# stm32f401_test_module.net
KiCad netlist of a schematic drawn in EAGLE
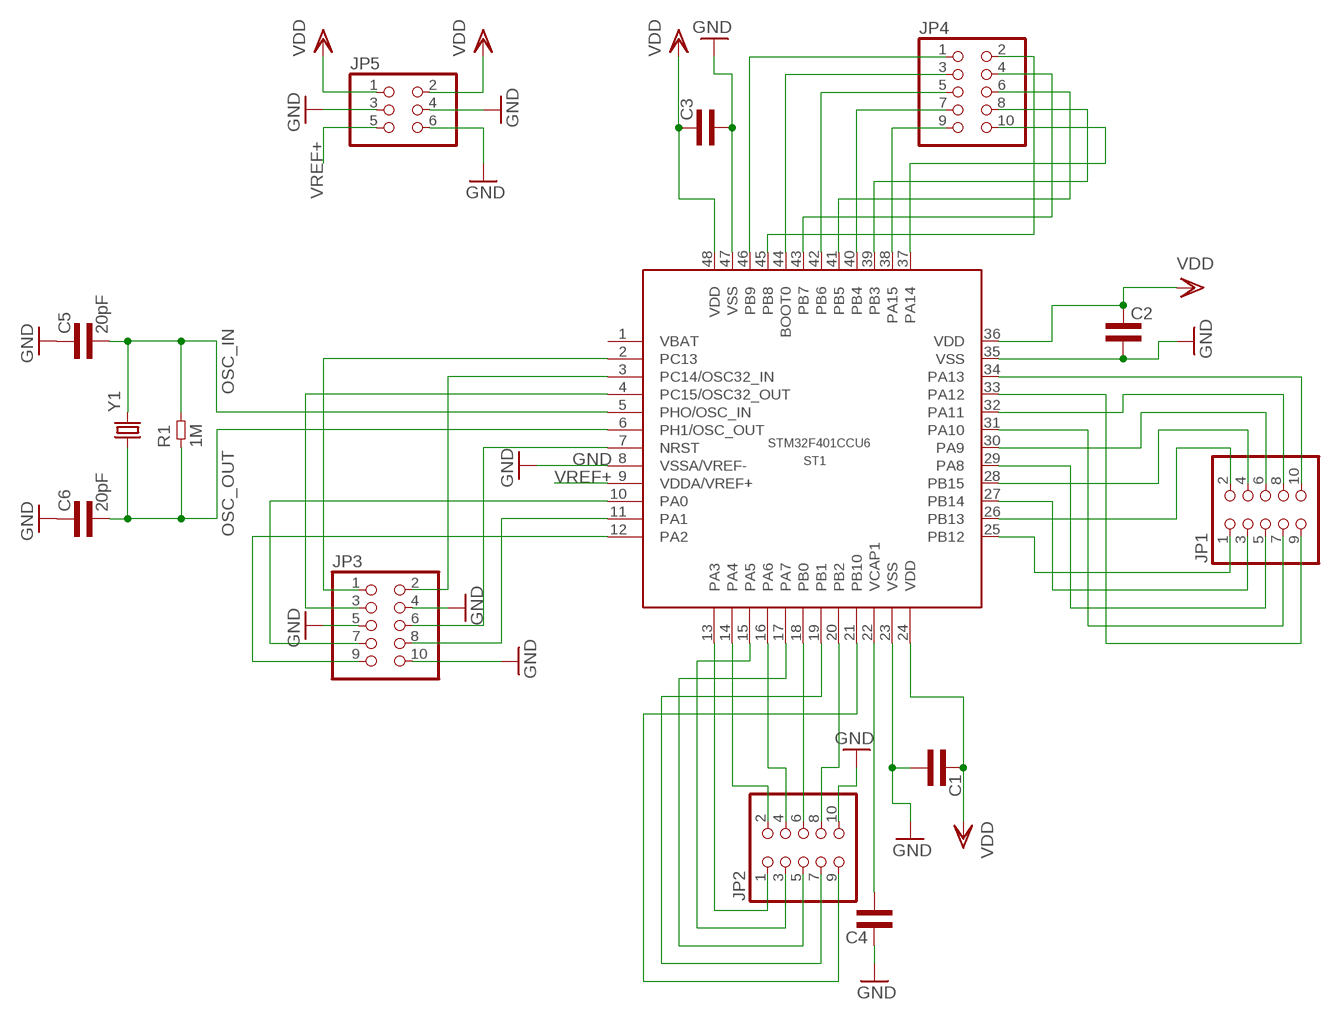
[diagram p0: schematic, sheet 1]

(export (version "E")
  (design (tool "Eeschema 10.0.6"))
  (components
    (comp (ref "C1")
      (value "CAP0402L3")
      (footprint "eagle-import:0402L3")
      (libsource (lib "eagle-import") (part "CAP0402L3"))
    )
    (comp (ref "C2")
      (value "CAP0402L3")
      (footprint "eagle-import:0402L3")
      (libsource (lib "eagle-import") (part "CAP0402L3"))
    )
    (comp (ref "C3")
      (value "CAP0402L3")
      (footprint "eagle-import:0402L3")
      (libsource (lib "eagle-import") (part "CAP0402L3"))
    )
    (comp (ref "C4")
      (value "CAP0402L3")
      (footprint "eagle-import:0402L3")
      (libsource (lib "eagle-import") (part "CAP0402L3"))
    )
    (comp (ref "C5")
      (value "20pF")
      (footprint "eagle-import:0603L3")
      (libsource (lib "eagle-import") (part "CAP0603L3"))
    )
    (comp (ref "C6")
      (value "20pF")
      (footprint "eagle-import:0603L3")
      (libsource (lib "eagle-import") (part "CAP0603L3"))
    )
    (comp (ref "JP1")
      (value "PINHD-2X5")
      (footprint "eagle-import:2X05")
      (libsource (lib "eagle-import") (part "PINHD-2X5"))
    )
    (comp (ref "JP2")
      (value "PINHD-2X5")
      (footprint "eagle-import:2X05")
      (libsource (lib "eagle-import") (part "PINHD-2X5"))
    )
    (comp (ref "JP3")
      (value "PINHD-2X5")
      (footprint "eagle-import:2X05")
      (libsource (lib "eagle-import") (part "PINHD-2X5"))
    )
    (comp (ref "JP4")
      (value "PINHD-2X5")
      (footprint "eagle-import:2X05")
      (libsource (lib "eagle-import") (part "PINHD-2X5"))
    )
    (comp (ref "JP5")
      (value "PINHD-2X3")
      (footprint "eagle-import:2X03")
      (libsource (lib "eagle-import") (part "PINHD-2X3"))
    )
    (comp (ref "R1")
      (value "1M")
      (footprint "eagle-import:0603L3")
      (libsource (lib "eagle-import") (part "RES0603L3"))
    )
    (comp (ref "ST1")
      (value "STM32F401CCU6")
      (footprint "eagle-import:UFQFPN48")
      (libsource (lib "eagle-import") (part "STM32F401CCU6"))
    )
    (comp (ref "Y1")
      (value "CRYSTALHC49US")
      (footprint "eagle-import:HC49US")
      (libsource (lib "eagle-import") (part "CRYSTALHC49US"))
    )
  )
  (nets
    (net (code "1") (name "/OSC_IN") (class "Default")
      (node (ref "C5") (pin "P$2") (pinfunction "2_P$2") (pintype "bidirectional"))
      (node (ref "R1") (pin "P$2") (pinfunction "2_P$2") (pintype "bidirectional"))
      (node (ref "ST1") (pin "5") (pinfunction "PHO/OSC_IN_5") (pintype "bidirectional"))
      (node (ref "Y1") (pin "2") (pinfunction "2_2") (pintype "passive"))
    )
    (net (code "2") (name "/OSC_OUT") (class "Default")
      (node (ref "C6") (pin "P$2") (pinfunction "2_P$2") (pintype "bidirectional"))
      (node (ref "R1") (pin "P$1") (pinfunction "1_P$1") (pintype "bidirectional"))
      (node (ref "ST1") (pin "6") (pinfunction "PH1/OSC_OUT_6") (pintype "bidirectional"))
      (node (ref "Y1") (pin "1") (pinfunction "1_1") (pintype "passive"))
    )
    (net (code "3") (name "/VREF+") (class "Default")
      (node (ref "JP5") (pin "5") (pinfunction "5_5") (pintype "passive"))
      (node (ref "ST1") (pin "9") (pinfunction "VDDA/VREF+_9") (pintype "bidirectional"))
    )
    (net (code "4") (name "GND") (class "Default")
      (node (ref "C1") (pin "P$2") (pinfunction "2_P$2") (pintype "bidirectional"))
      (node (ref "C2") (pin "P$2") (pinfunction "2_P$2") (pintype "bidirectional"))
      (node (ref "C3") (pin "P$2") (pinfunction "2_P$2") (pintype "bidirectional"))
      (node (ref "C4") (pin "P$1") (pinfunction "1_P$1") (pintype "bidirectional"))
      (node (ref "C5") (pin "P$1") (pinfunction "1_P$1") (pintype "bidirectional"))
      (node (ref "C6") (pin "P$1") (pinfunction "1_P$1") (pintype "bidirectional"))
      (node (ref "JP2") (pin "10") (pinfunction "10_10") (pintype "passive"))
      (node (ref "JP3") (pin "10") (pinfunction "10_10") (pintype "passive"))
      (node (ref "JP3") (pin "4") (pinfunction "4_4") (pintype "passive"))
      (node (ref "JP3") (pin "5") (pinfunction "5_5") (pintype "passive"))
      (node (ref "JP5") (pin "3") (pinfunction "3_3") (pintype "passive"))
      (node (ref "JP5") (pin "4") (pinfunction "4_4") (pintype "passive"))
      (node (ref "JP5") (pin "6") (pinfunction "6_6") (pintype "passive"))
      (node (ref "ST1") (pin "23") (pinfunction "VSS_23") (pintype "bidirectional"))
      (node (ref "ST1") (pin "35") (pinfunction "VSS_35") (pintype "bidirectional"))
      (node (ref "ST1") (pin "47") (pinfunction "VSS_47") (pintype "bidirectional"))
      (node (ref "ST1") (pin "8") (pinfunction "VSSA/VREF-_8") (pintype "bidirectional"))
    )
    (net (code "5") (name "Net-(C4-2)") (class "Default")
      (node (ref "C4") (pin "P$2") (pinfunction "2_P$2") (pintype "bidirectional"))
      (node (ref "ST1") (pin "22") (pinfunction "VCAP1_22") (pintype "bidirectional"))
    )
    (net (code "6") (name "Net-(ST1-BOOT0)") (class "Default")
      (node (ref "JP4") (pin "3") (pinfunction "3_3") (pintype "passive"))
      (node (ref "ST1") (pin "44") (pinfunction "BOOT0_44") (pintype "bidirectional"))
    )
    (net (code "7") (name "Net-(ST1-NRST)") (class "Default")
      (node (ref "JP3") (pin "6") (pinfunction "6_6") (pintype "passive"))
      (node (ref "ST1") (pin "7") (pinfunction "NRST_7") (pintype "bidirectional"))
    )
    (net (code "8") (name "Net-(ST1-PA0)") (class "Default")
      (node (ref "JP3") (pin "7") (pinfunction "7_7") (pintype "passive"))
      (node (ref "ST1") (pin "10") (pinfunction "PA0_10") (pintype "bidirectional"))
    )
    (net (code "9") (name "Net-(ST1-PA1)") (class "Default")
      (node (ref "JP3") (pin "8") (pinfunction "8_8") (pintype "passive"))
      (node (ref "ST1") (pin "11") (pinfunction "PA1_11") (pintype "bidirectional"))
    )
    (net (code "10") (name "Net-(ST1-PA2)") (class "Default")
      (node (ref "JP3") (pin "9") (pinfunction "9_9") (pintype "passive"))
      (node (ref "ST1") (pin "12") (pinfunction "PA2_12") (pintype "bidirectional"))
    )
    (net (code "11") (name "Net-(ST1-PA3)") (class "Default")
      (node (ref "JP2") (pin "1") (pinfunction "1_1") (pintype "passive"))
      (node (ref "ST1") (pin "13") (pinfunction "PA3_13") (pintype "bidirectional"))
    )
    (net (code "12") (name "Net-(ST1-PA4)") (class "Default")
      (node (ref "JP2") (pin "2") (pinfunction "2_2") (pintype "passive"))
      (node (ref "ST1") (pin "14") (pinfunction "PA4_14") (pintype "bidirectional"))
    )
    (net (code "13") (name "Net-(ST1-PA5)") (class "Default")
      (node (ref "JP2") (pin "3") (pinfunction "3_3") (pintype "passive"))
      (node (ref "ST1") (pin "15") (pinfunction "PA5_15") (pintype "bidirectional"))
    )
    (net (code "14") (name "Net-(ST1-PA6)") (class "Default")
      (node (ref "JP2") (pin "4") (pinfunction "4_4") (pintype "passive"))
      (node (ref "ST1") (pin "16") (pinfunction "PA6_16") (pintype "bidirectional"))
    )
    (net (code "15") (name "Net-(ST1-PA7)") (class "Default")
      (node (ref "JP2") (pin "5") (pinfunction "5_5") (pintype "passive"))
      (node (ref "ST1") (pin "17") (pinfunction "PA7_17") (pintype "bidirectional"))
    )
    (net (code "16") (name "Net-(ST1-PA8)") (class "Default")
      (node (ref "JP1") (pin "5") (pinfunction "5_5") (pintype "passive"))
      (node (ref "ST1") (pin "29") (pinfunction "PA8_29") (pintype "bidirectional"))
    )
    (net (code "17") (name "Net-(ST1-PA9)") (class "Default")
      (node (ref "JP1") (pin "6") (pinfunction "6_6") (pintype "passive"))
      (node (ref "ST1") (pin "30") (pinfunction "PA9_30") (pintype "bidirectional"))
    )
    (net (code "18") (name "Net-(ST1-PA10)") (class "Default")
      (node (ref "JP1") (pin "7") (pinfunction "7_7") (pintype "passive"))
      (node (ref "ST1") (pin "31") (pinfunction "PA10_31") (pintype "bidirectional"))
    )
    (net (code "19") (name "Net-(ST1-PA11)") (class "Default")
      (node (ref "JP1") (pin "8") (pinfunction "8_8") (pintype "passive"))
      (node (ref "ST1") (pin "32") (pinfunction "PA11_32") (pintype "bidirectional"))
    )
    (net (code "20") (name "Net-(ST1-PA12)") (class "Default")
      (node (ref "JP1") (pin "9") (pinfunction "9_9") (pintype "passive"))
      (node (ref "ST1") (pin "33") (pinfunction "PA12_33") (pintype "bidirectional"))
    )
    (net (code "21") (name "Net-(ST1-PA13)") (class "Default")
      (node (ref "JP1") (pin "10") (pinfunction "10_10") (pintype "passive"))
      (node (ref "ST1") (pin "34") (pinfunction "PA13_34") (pintype "bidirectional"))
    )
    (net (code "22") (name "Net-(ST1-PA14)") (class "Default")
      (node (ref "JP4") (pin "10") (pinfunction "10_10") (pintype "passive"))
      (node (ref "ST1") (pin "37") (pinfunction "PA14_37") (pintype "bidirectional"))
    )
    (net (code "23") (name "Net-(ST1-PA15)") (class "Default")
      (node (ref "JP4") (pin "9") (pinfunction "9_9") (pintype "passive"))
      (node (ref "ST1") (pin "38") (pinfunction "PA15_38") (pintype "bidirectional"))
    )
    (net (code "24") (name "Net-(ST1-PB0)") (class "Default")
      (node (ref "JP2") (pin "6") (pinfunction "6_6") (pintype "passive"))
      (node (ref "ST1") (pin "18") (pinfunction "PB0_18") (pintype "bidirectional"))
    )
    (net (code "25") (name "Net-(ST1-PB1)") (class "Default")
      (node (ref "JP2") (pin "7") (pinfunction "7_7") (pintype "passive"))
      (node (ref "ST1") (pin "19") (pinfunction "PB1_19") (pintype "bidirectional"))
    )
    (net (code "26") (name "Net-(ST1-PB2)") (class "Default")
      (node (ref "JP2") (pin "8") (pinfunction "8_8") (pintype "passive"))
      (node (ref "ST1") (pin "20") (pinfunction "PB2_20") (pintype "bidirectional"))
    )
    (net (code "27") (name "Net-(ST1-PB3)") (class "Default")
      (node (ref "JP4") (pin "8") (pinfunction "8_8") (pintype "passive"))
      (node (ref "ST1") (pin "39") (pinfunction "PB3_39") (pintype "bidirectional"))
    )
    (net (code "28") (name "Net-(ST1-PB4)") (class "Default")
      (node (ref "JP4") (pin "7") (pinfunction "7_7") (pintype "passive"))
      (node (ref "ST1") (pin "40") (pinfunction "PB4_40") (pintype "bidirectional"))
    )
    (net (code "29") (name "Net-(ST1-PB5)") (class "Default")
      (node (ref "JP4") (pin "6") (pinfunction "6_6") (pintype "passive"))
      (node (ref "ST1") (pin "41") (pinfunction "PB5_41") (pintype "bidirectional"))
    )
    (net (code "30") (name "Net-(ST1-PB6)") (class "Default")
      (node (ref "JP4") (pin "5") (pinfunction "5_5") (pintype "passive"))
      (node (ref "ST1") (pin "42") (pinfunction "PB6_42") (pintype "bidirectional"))
    )
    (net (code "31") (name "Net-(ST1-PB7)") (class "Default")
      (node (ref "JP4") (pin "4") (pinfunction "4_4") (pintype "passive"))
      (node (ref "ST1") (pin "43") (pinfunction "PB7_43") (pintype "bidirectional"))
    )
    (net (code "32") (name "Net-(ST1-PB8)") (class "Default")
      (node (ref "JP4") (pin "2") (pinfunction "2_2") (pintype "passive"))
      (node (ref "ST1") (pin "45") (pinfunction "PB8_45") (pintype "bidirectional"))
    )
    (net (code "33") (name "Net-(ST1-PB9)") (class "Default")
      (node (ref "JP4") (pin "1") (pinfunction "1_1") (pintype "passive"))
      (node (ref "ST1") (pin "46") (pinfunction "PB9_46") (pintype "bidirectional"))
    )
    (net (code "34") (name "Net-(ST1-PB10)") (class "Default")
      (node (ref "JP2") (pin "9") (pinfunction "9_9") (pintype "passive"))
      (node (ref "ST1") (pin "21") (pinfunction "PB10_21") (pintype "bidirectional"))
    )
    (net (code "35") (name "Net-(ST1-PB12)") (class "Default")
      (node (ref "JP1") (pin "1") (pinfunction "1_1") (pintype "passive"))
      (node (ref "ST1") (pin "25") (pinfunction "PB12_25") (pintype "bidirectional"))
    )
    (net (code "36") (name "Net-(ST1-PB13)") (class "Default")
      (node (ref "JP1") (pin "2") (pinfunction "2_2") (pintype "passive"))
      (node (ref "ST1") (pin "26") (pinfunction "PB13_26") (pintype "bidirectional"))
    )
    (net (code "37") (name "Net-(ST1-PB14)") (class "Default")
      (node (ref "JP1") (pin "3") (pinfunction "3_3") (pintype "passive"))
      (node (ref "ST1") (pin "27") (pinfunction "PB14_27") (pintype "bidirectional"))
    )
    (net (code "38") (name "Net-(ST1-PB15)") (class "Default")
      (node (ref "JP1") (pin "4") (pinfunction "4_4") (pintype "passive"))
      (node (ref "ST1") (pin "28") (pinfunction "PB15_28") (pintype "bidirectional"))
    )
    (net (code "39") (name "Net-(ST1-PC13)") (class "Default")
      (node (ref "JP3") (pin "1") (pinfunction "1_1") (pintype "passive"))
      (node (ref "ST1") (pin "2") (pinfunction "PC13_2") (pintype "bidirectional"))
    )
    (net (code "40") (name "Net-(ST1-PC14{slash}OSC32_IN)") (class "Default")
      (node (ref "JP3") (pin "2") (pinfunction "2_2") (pintype "passive"))
      (node (ref "ST1") (pin "3") (pinfunction "PC14/OSC32_IN_3") (pintype "bidirectional"))
    )
    (net (code "41") (name "Net-(ST1-PC15{slash}OSC32_OUT)") (class "Default")
      (node (ref "JP3") (pin "3") (pinfunction "3_3") (pintype "passive"))
      (node (ref "ST1") (pin "4") (pinfunction "PC15/OSC32_OUT_4") (pintype "bidirectional"))
    )
    (net (code "42") (name "VDD") (class "Default")
      (node (ref "C1") (pin "P$1") (pinfunction "1_P$1") (pintype "bidirectional"))
      (node (ref "C2") (pin "P$1") (pinfunction "1_P$1") (pintype "bidirectional"))
      (node (ref "C3") (pin "P$1") (pinfunction "1_P$1") (pintype "bidirectional"))
      (node (ref "JP5") (pin "1") (pinfunction "1_1") (pintype "passive"))
      (node (ref "JP5") (pin "2") (pinfunction "2_2") (pintype "passive"))
      (node (ref "ST1") (pin "24") (pinfunction "VDD_24") (pintype "bidirectional"))
      (node (ref "ST1") (pin "36") (pinfunction "VDD_36") (pintype "bidirectional"))
      (node (ref "ST1") (pin "48") (pinfunction "VDD_48") (pintype "bidirectional"))
    )
    (net (code "43") (name "unconnected-(ST1-VBAT-Pad1)") (class "Default")
      (node (ref "ST1") (pin "1") (pinfunction "VBAT_1") (pintype "bidirectional"))
    )
  )
)
